# Shared.net
KiCad netlist of a schematic drawn in Altium Designer
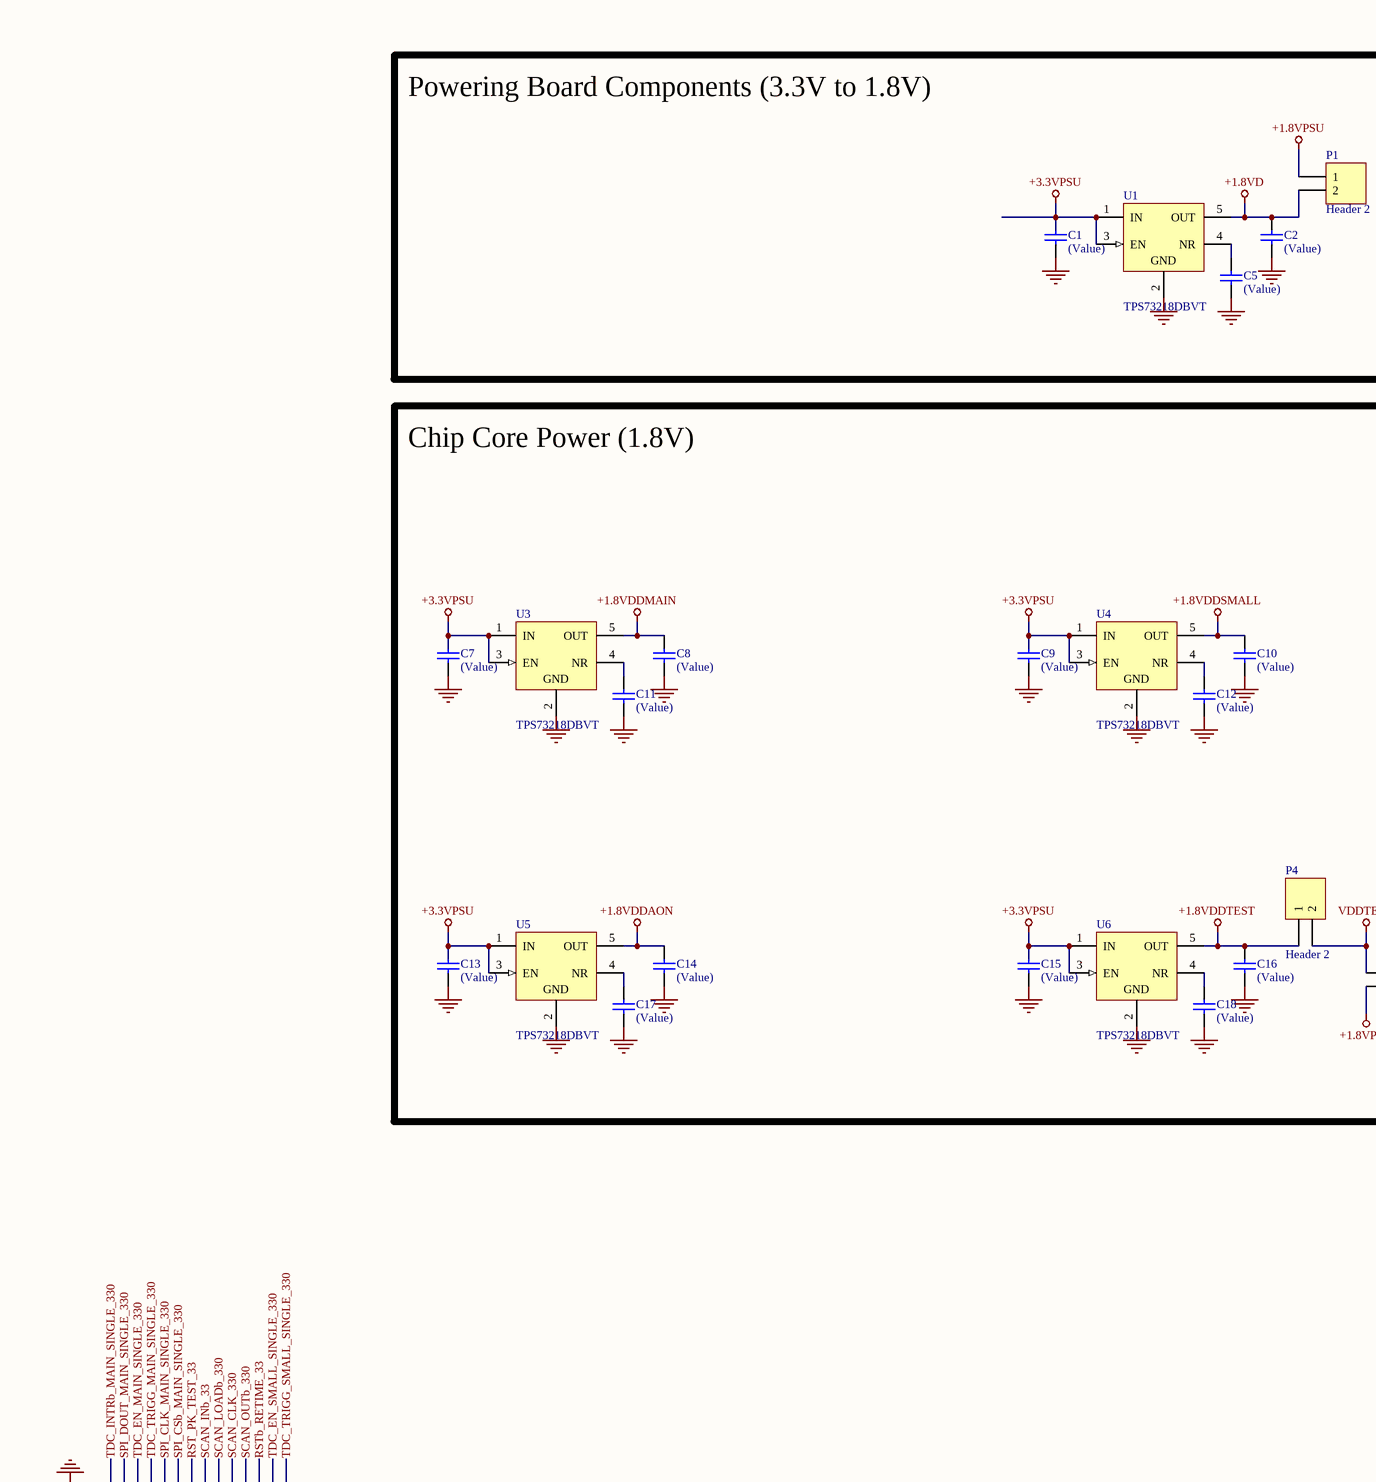
[diagram p0: Shared.SchDoc, top left]
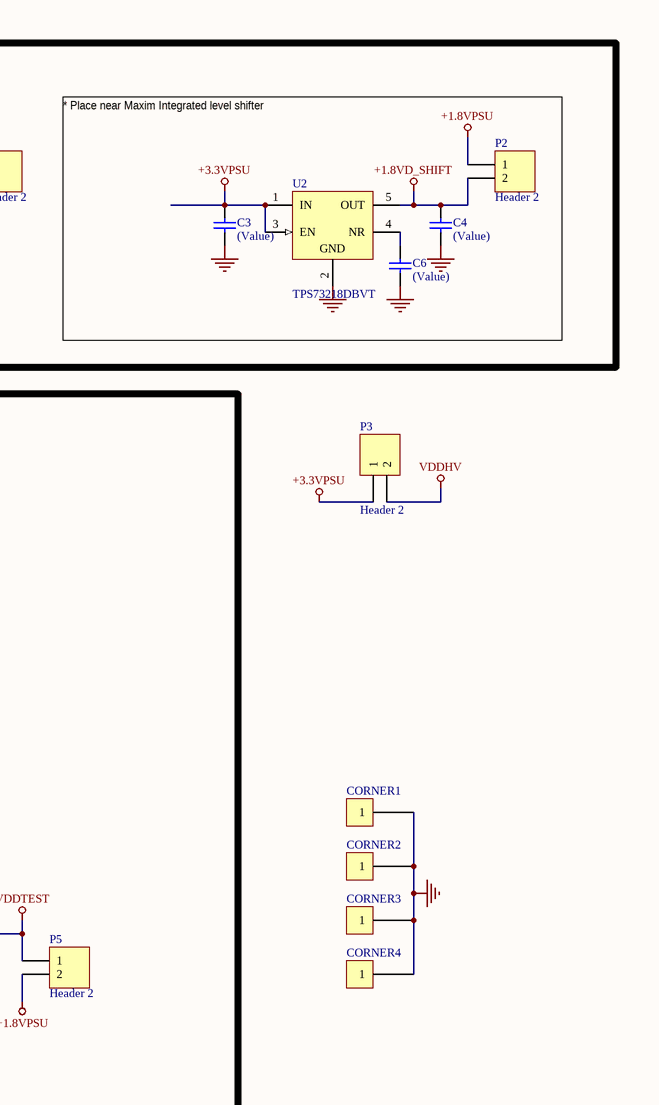
[diagram p1: Shared.SchDoc, top right]
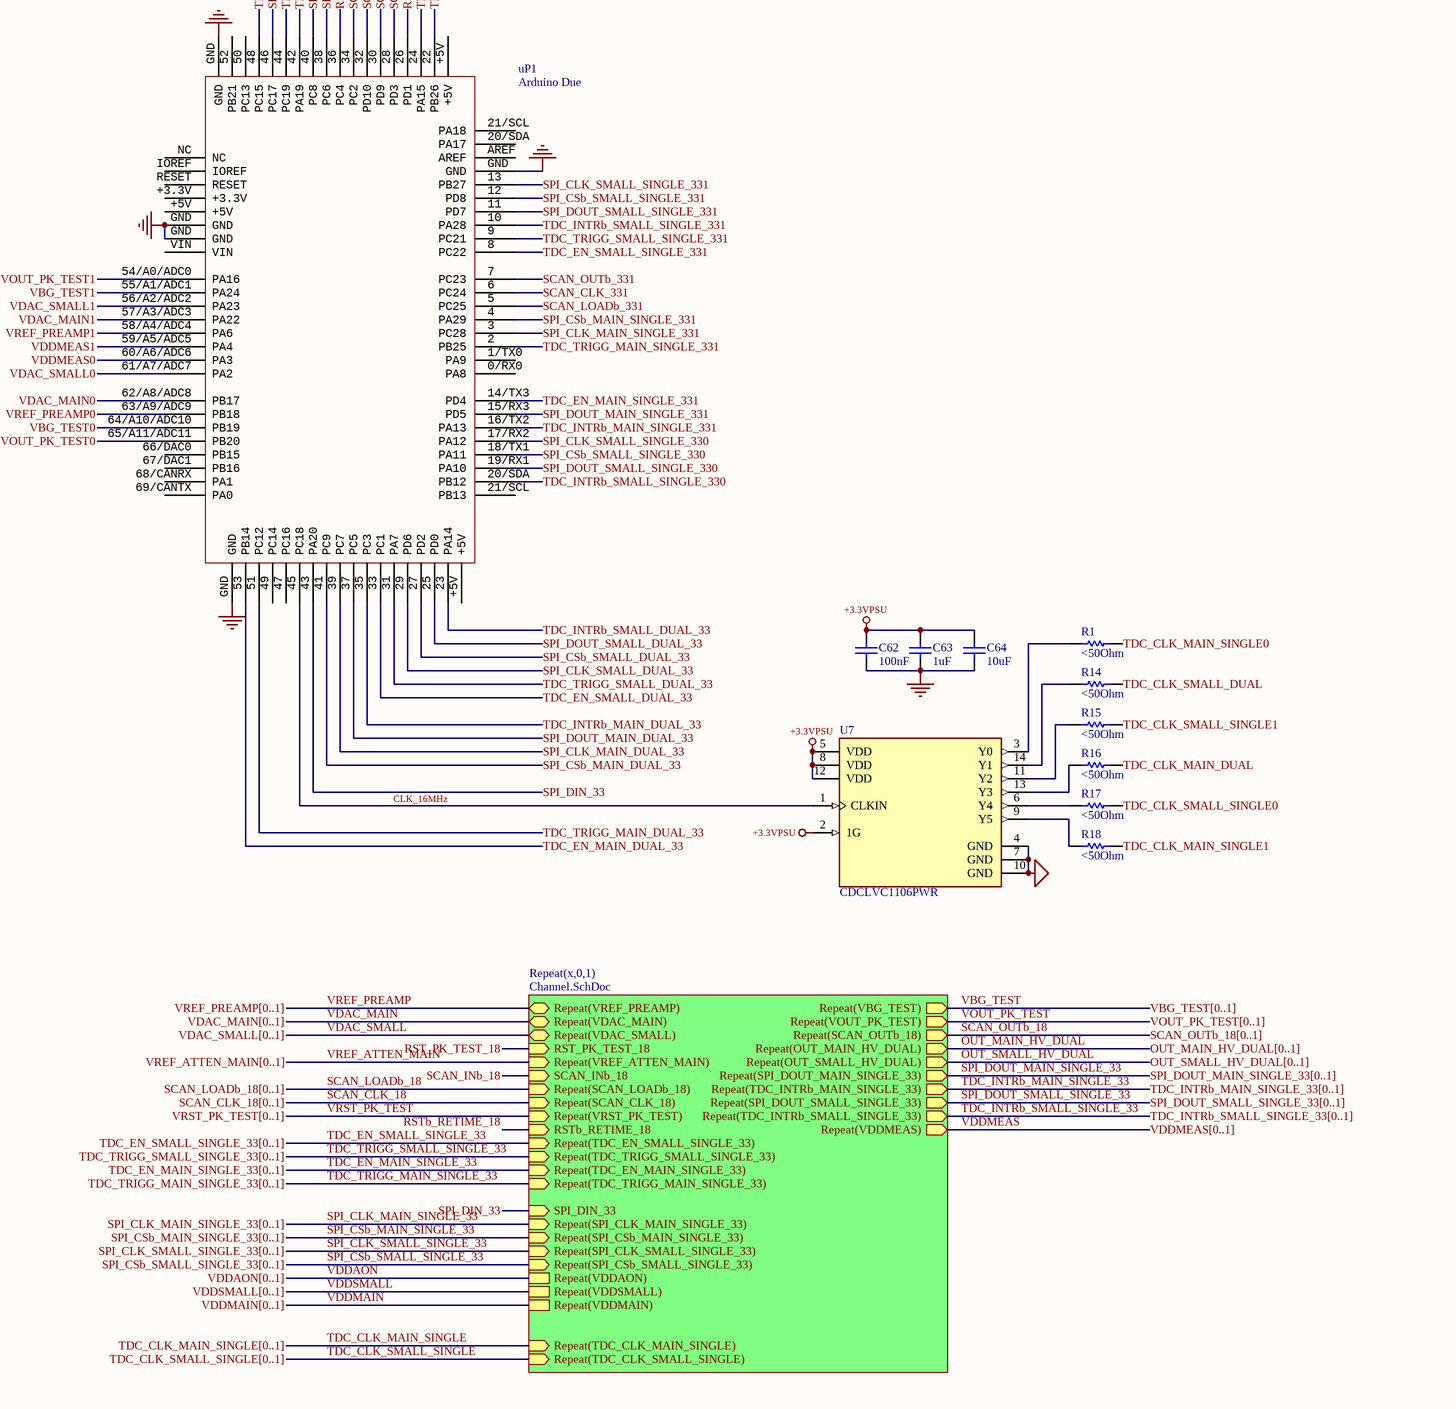
[diagram p2: Shared.SchDoc, bottom left]
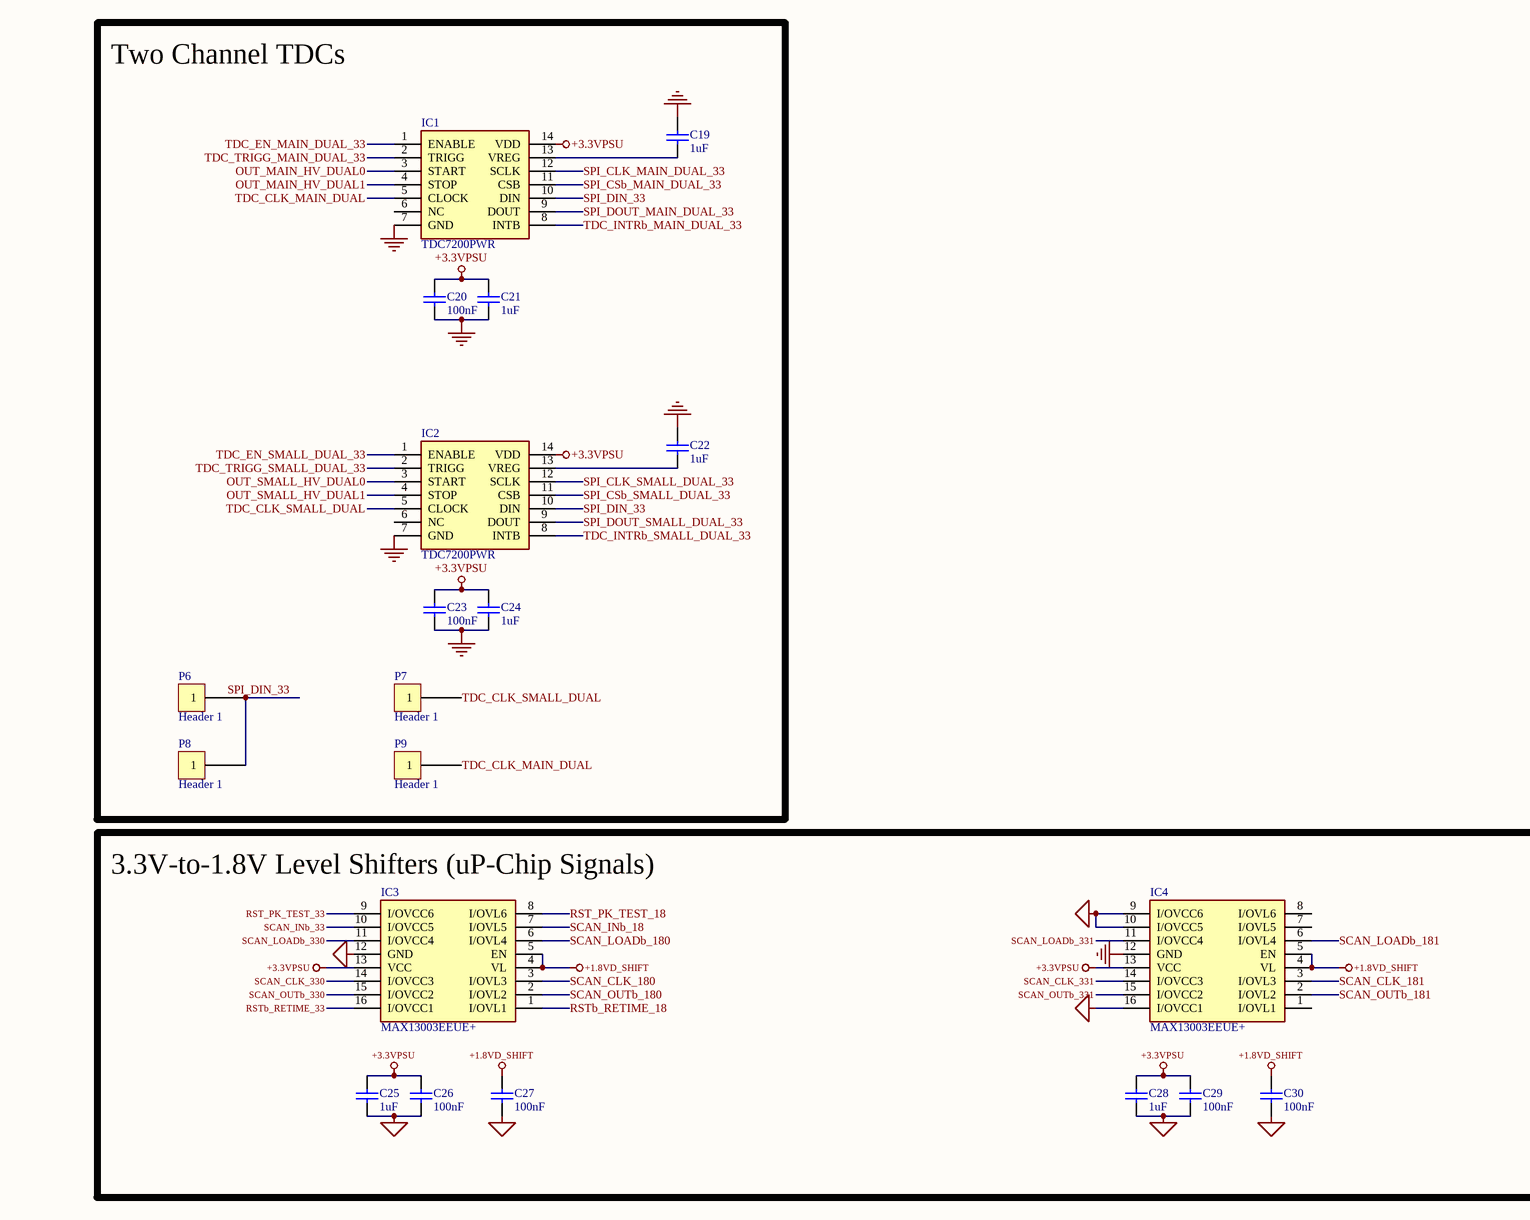
[diagram p3: Shared.SchDoc, bottom right]

(export (version "E")
  (design (tool "Eeschema 10.0.6"))
  (components
    (comp (ref "C1")
      (value "(Value)")
      (footprint "CAPC1608X90X35ML10T15")
      (description "0603")
      (fields (field (name "MANUFACTURER") "Murata"))
      (libsource (lib "Altium Content Vault") (part "CAP-NP-2"))
    )
    (comp (ref "C2")
      (value "(Value)")
      (footprint "CAPC1608X90X35ML10T15")
      (description "0603")
      (fields (field (name "MANUFACTURER") "Murata"))
      (libsource (lib "Altium Content Vault") (part "CAP-NP-2"))
    )
    (comp (ref "C3")
      (value "(Value)")
      (footprint "CAPC1608X90X35ML10T15")
      (description "0603")
      (fields (field (name "MANUFACTURER") "Murata"))
      (libsource (lib "Altium Content Vault") (part "CAP-NP-2"))
    )
    (comp (ref "C4")
      (value "(Value)")
      (footprint "CAPC1608X90X35ML10T15")
      (description "0603")
      (fields (field (name "MANUFACTURER") "Murata"))
      (libsource (lib "Altium Content Vault") (part "CAP-NP-2"))
    )
    (comp (ref "C5")
      (value "(Value)")
      (footprint "CAPC1608X90X35ML10T15")
      (description "0603")
      (fields (field (name "MANUFACTURER") "Murata"))
      (libsource (lib "Altium Content Vault") (part "CAP-NP-2"))
    )
    (comp (ref "C6")
      (value "(Value)")
      (footprint "CAPC1608X90X35ML10T15")
      (description "0603")
      (fields (field (name "MANUFACTURER") "Murata"))
      (libsource (lib "Altium Content Vault") (part "CAP-NP-2"))
    )
    (comp (ref "C7")
      (value "(Value)")
      (footprint "CAPC1608X90X35ML10T15")
      (description "0603")
      (fields (field (name "MANUFACTURER") "Murata"))
      (libsource (lib "Altium Content Vault") (part "CAP-NP-2"))
    )
    (comp (ref "C8")
      (value "(Value)")
      (footprint "CAPC1608X90X35ML10T15")
      (description "0603")
      (fields (field (name "MANUFACTURER") "Murata"))
      (libsource (lib "Altium Content Vault") (part "CAP-NP-2"))
    )
    (comp (ref "C9")
      (value "(Value)")
      (footprint "CAPC1608X90X35ML10T15")
      (description "0603")
      (fields (field (name "MANUFACTURER") "Murata"))
      (libsource (lib "Altium Content Vault") (part "CAP-NP-2"))
    )
    (comp (ref "C10")
      (value "(Value)")
      (footprint "CAPC1608X90X35ML10T15")
      (description "0603")
      (fields (field (name "MANUFACTURER") "Murata"))
      (libsource (lib "Altium Content Vault") (part "CAP-NP-2"))
    )
    (comp (ref "C11")
      (value "(Value)")
      (footprint "CAPC1608X90X35ML10T15")
      (description "0603")
      (fields (field (name "MANUFACTURER") "Murata"))
      (libsource (lib "Altium Content Vault") (part "CAP-NP-2"))
    )
    (comp (ref "C12")
      (value "(Value)")
      (footprint "CAPC1608X90X35ML10T15")
      (description "0603")
      (fields (field (name "MANUFACTURER") "Murata"))
      (libsource (lib "Altium Content Vault") (part "CAP-NP-2"))
    )
    (comp (ref "C13")
      (value "(Value)")
      (footprint "CAPC1608X90X35ML10T15")
      (description "0603")
      (fields (field (name "MANUFACTURER") "Murata"))
      (libsource (lib "Altium Content Vault") (part "CAP-NP-2"))
    )
    (comp (ref "C14")
      (value "(Value)")
      (footprint "CAPC1608X90X35ML10T15")
      (description "0603")
      (fields (field (name "MANUFACTURER") "Murata"))
      (libsource (lib "Altium Content Vault") (part "CAP-NP-2"))
    )
    (comp (ref "C15")
      (value "(Value)")
      (footprint "CAPC1608X90X35ML10T15")
      (description "0603")
      (fields (field (name "MANUFACTURER") "Murata"))
      (libsource (lib "Altium Content Vault") (part "CAP-NP-2"))
    )
    (comp (ref "C16")
      (value "(Value)")
      (footprint "CAPC1608X90X35ML10T15")
      (description "0603")
      (fields (field (name "MANUFACTURER") "Murata"))
      (libsource (lib "Altium Content Vault") (part "CAP-NP-2"))
    )
    (comp (ref "C17")
      (value "(Value)")
      (footprint "CAPC1608X90X35ML10T15")
      (description "0603")
      (fields (field (name "MANUFACTURER") "Murata"))
      (libsource (lib "Altium Content Vault") (part "CAP-NP-2"))
    )
    (comp (ref "C18")
      (value "(Value)")
      (footprint "CAPC1608X90X35ML10T15")
      (description "0603")
      (fields (field (name "MANUFACTURER") "Murata"))
      (libsource (lib "Altium Content Vault") (part "CAP-NP-2"))
    )
    (comp (ref "C19")
      (value "1uF")
      (footprint "CAPC1608X90X35ML10T15")
      (description "0603")
      (fields (field (name "MANUFACTURER") "Murata"))
      (libsource (lib "Altium Content Vault") (part "CAP-NP-2"))
    )
    (comp (ref "C20")
      (value "100nF")
      (footprint "CAPC1608X90X35ML10T15")
      (description "0603")
      (fields (field (name "MANUFACTURER") "Murata"))
      (libsource (lib "Altium Content Vault") (part "CAP-NP-2"))
    )
    (comp (ref "C21")
      (value "1uF")
      (footprint "CAPC1608X90X35ML10T15")
      (description "0603")
      (fields (field (name "MANUFACTURER") "Murata"))
      (libsource (lib "Altium Content Vault") (part "CAP-NP-2"))
    )
    (comp (ref "C22")
      (value "1uF")
      (footprint "CAPC1608X90X35ML10T15")
      (description "0603")
      (fields (field (name "MANUFACTURER") "Murata"))
      (libsource (lib "Altium Content Vault") (part "CAP-NP-2"))
    )
    (comp (ref "C23")
      (value "100nF")
      (footprint "CAPC1608X90X35ML10T15")
      (description "0603")
      (fields (field (name "MANUFACTURER") "Murata"))
      (libsource (lib "Altium Content Vault") (part "CAP-NP-2"))
    )
    (comp (ref "C24")
      (value "1uF")
      (footprint "CAPC1608X90X35ML10T15")
      (description "0603")
      (fields (field (name "MANUFACTURER") "Murata"))
      (libsource (lib "Altium Content Vault") (part "CAP-NP-2"))
    )
    (comp (ref "C25")
      (value "1uF")
      (footprint "CAPC1608X90X35ML10T15")
      (description "0603")
      (fields (field (name "MANUFACTURER") "Murata"))
      (libsource (lib "Altium Content Vault") (part "CAP-NP-2"))
    )
    (comp (ref "C26")
      (value "100nF")
      (footprint "CAPC1608X90X35ML10T15")
      (description "0603")
      (fields (field (name "MANUFACTURER") "Murata"))
      (libsource (lib "Altium Content Vault") (part "CAP-NP-2"))
    )
    (comp (ref "C27")
      (value "100nF")
      (footprint "CAPC1608X90X35ML10T15")
      (description "0603")
      (fields (field (name "MANUFACTURER") "Murata"))
      (libsource (lib "Altium Content Vault") (part "CAP-NP-2"))
    )
    (comp (ref "C28")
      (value "1uF")
      (footprint "CAPC1608X90X35ML10T15")
      (description "0603")
      (fields (field (name "MANUFACTURER") "Murata"))
      (libsource (lib "Altium Content Vault") (part "CAP-NP-2"))
    )
    (comp (ref "C29")
      (value "100nF")
      (footprint "CAPC1608X90X35ML10T15")
      (description "0603")
      (fields (field (name "MANUFACTURER") "Murata"))
      (libsource (lib "Altium Content Vault") (part "CAP-NP-2"))
    )
    (comp (ref "C30")
      (value "100nF")
      (footprint "CAPC1608X90X35ML10T15")
      (description "0603")
      (fields (field (name "MANUFACTURER") "Murata"))
      (libsource (lib "Altium Content Vault") (part "CAP-NP-2"))
    )
    (comp (ref "C62")
      (value "100nF")
      (footprint "CAPC1608X90X35ML10T15")
      (description "0603")
      (fields (field (name "MANUFACTURER") "Murata"))
      (libsource (lib "Altium Content Vault") (part "CAP-NP-2"))
    )
    (comp (ref "C63")
      (value "1uF")
      (footprint "CAPC1608X90X35ML10T15")
      (description "0603")
      (fields (field (name "MANUFACTURER") "Murata"))
      (libsource (lib "Altium Content Vault") (part "CAP-NP-2"))
    )
    (comp (ref "C64")
      (value "10uF")
      (footprint "CAPC1608X90X35ML10T15")
      (description "0603")
      (fields (field (name "MANUFACTURER") "Murata"))
      (libsource (lib "Altium Content Vault") (part "CAP-NP-2"))
    )
    (comp (ref "CORNER1")
      (value "Corner Mount")
      (footprint "CornerMount")
      (libsource (lib "intlib") (part "Corner Mount"))
    )
    (comp (ref "CORNER2")
      (value "Corner Mount")
      (footprint "CornerMount")
      (libsource (lib "intlib") (part "Corner Mount"))
    )
    (comp (ref "CORNER3")
      (value "Corner Mount")
      (footprint "CornerMount")
      (libsource (lib "intlib") (part "Corner Mount"))
    )
    (comp (ref "CORNER4")
      (value "Corner Mount")
      (footprint "CornerMount")
      (libsource (lib "intlib") (part "Corner Mount"))
    )
    (comp (ref "IC1")
      (value "TDC7200PWR")
      (footprint "SamacSys:SOP65P640X120-14N")
      (description "Integrated Circuit")
      (libsource (lib "*") (part "TDC7200PWR"))
    )
    (comp (ref "IC2")
      (value "TDC7200PWR")
      (footprint "SamacSys:SOP65P640X120-14N")
      (description "Integrated Circuit")
      (libsource (lib "*") (part "TDC7200PWR"))
    )
    (comp (ref "IC3")
      (value "MAX13003EEUE+")
      (footprint "SamacSys:SOP65P640X110-16N")
      (description "Integrated Circuit")
      (libsource (lib "*") (part "MAX13003EEUE+"))
    )
    (comp (ref "IC4")
      (value "MAX13003EEUE+")
      (footprint "SamacSys:SOP65P640X110-16N")
      (description "Integrated Circuit")
      (libsource (lib "*") (part "MAX13003EEUE+"))
    )
    (comp (ref "P1")
      (value "Header 2")
      (footprint "HDR1X2")
      (description "Header, 2-Pin")
      (fields (field (name "PUBLISHER") "Altium Limited"))
      (libsource (lib "") (part "Header 2_1"))
    )
    (comp (ref "P2")
      (value "Header 2")
      (footprint "HDR1X2")
      (description "Header, 2-Pin")
      (fields (field (name "PUBLISHER") "Altium Limited"))
      (libsource (lib "") (part "Header 2_1"))
    )
    (comp (ref "P3")
      (value "Header 2")
      (footprint "HDR1X2")
      (description "Header, 2-Pin")
      (fields (field (name "PUBLISHER") "Altium Limited"))
      (libsource (lib "Miscellaneous Connectors") (part "Header 2"))
    )
    (comp (ref "P4")
      (value "Header 2")
      (footprint "HDR1X2")
      (description "Header, 2-Pin")
      (fields (field (name "PUBLISHER") "Altium Limited"))
      (libsource (lib "Miscellaneous Connectors") (part "Header 2"))
    )
    (comp (ref "P5")
      (value "Header 2")
      (footprint "HDR1X2")
      (description "Header, 2-Pin")
      (fields (field (name "PUBLISHER") "Altium Limited"))
      (libsource (lib "") (part "Header 2_1"))
    )
    (comp (ref "P6") (value "Header 1") (footprint "Header1") (libsource (lib "intlib") (part "Header 1")))
    (comp (ref "P7") (value "Header 1") (footprint "Header1") (libsource (lib "intlib") (part "Header 1")))
    (comp (ref "P8") (value "Header 1") (footprint "Header1") (libsource (lib "intlib") (part "Header 1")))
    (comp (ref "P9") (value "Header 1") (footprint "Header1") (libsource (lib "intlib") (part "Header 1")))
    (comp (ref "R1")
      (value "<50Ohm")
      (footprint "RESC1609X50X30NL8T20")
      (description "0603")
      (fields (field (name "MANUFACTURER") "Vishay Semiconductor"))
      (libsource (lib "Altium Content Vault") (part "RES-2"))
    )
    (comp (ref "R14")
      (value "<50Ohm")
      (footprint "RESC1609X50X30NL8T20")
      (description "0603")
      (fields (field (name "MANUFACTURER") "Vishay Semiconductor"))
      (libsource (lib "Altium Content Vault") (part "RES-2"))
    )
    (comp (ref "R15")
      (value "<50Ohm")
      (footprint "RESC1609X50X30NL8T20")
      (description "0603")
      (fields (field (name "MANUFACTURER") "Vishay Semiconductor"))
      (libsource (lib "Altium Content Vault") (part "RES-2"))
    )
    (comp (ref "R16")
      (value "<50Ohm")
      (footprint "RESC1609X50X30NL8T20")
      (description "0603")
      (fields (field (name "MANUFACTURER") "Vishay Semiconductor"))
      (libsource (lib "Altium Content Vault") (part "RES-2"))
    )
    (comp (ref "R17")
      (value "<50Ohm")
      (footprint "RESC1609X50X30NL8T20")
      (description "0603")
      (fields (field (name "MANUFACTURER") "Vishay Semiconductor"))
      (libsource (lib "Altium Content Vault") (part "RES-2"))
    )
    (comp (ref "R18")
      (value "<50Ohm")
      (footprint "RESC1609X50X30NL8T20")
      (description "0603")
      (fields (field (name "MANUFACTURER") "Vishay Semiconductor"))
      (libsource (lib "Altium Content Vault") (part "RES-2"))
    )
    (comp (ref "U1")
      (value "TPS73218DBVT")
      (footprint "DBV0005A_N")
      (fields (field (name "MANUFACTURER") "Texas Instruments"))
      (libsource (lib "Altium Content Vault") (part "TI-TPS79NXX-YYSOT5"))
    )
    (comp (ref "U2")
      (value "TPS73218DBVT")
      (footprint "DBV0005A_N")
      (fields (field (name "MANUFACTURER") "Texas Instruments"))
      (libsource (lib "Altium Content Vault") (part "TI-TPS79NXX-YYSOT5"))
    )
    (comp (ref "U3")
      (value "TPS73218DBVT")
      (footprint "DBV0005A_N")
      (fields (field (name "MANUFACTURER") "Texas Instruments"))
      (libsource (lib "Altium Content Vault") (part "TI-TPS79NXX-YYSOT5"))
    )
    (comp (ref "U4")
      (value "TPS73218DBVT")
      (footprint "DBV0005A_N")
      (fields (field (name "MANUFACTURER") "Texas Instruments"))
      (libsource (lib "Altium Content Vault") (part "TI-TPS79NXX-YYSOT5"))
    )
    (comp (ref "U5")
      (value "TPS73218DBVT")
      (footprint "DBV0005A_N")
      (fields (field (name "MANUFACTURER") "Texas Instruments"))
      (libsource (lib "Altium Content Vault") (part "TI-TPS79NXX-YYSOT5"))
    )
    (comp (ref "U6")
      (value "TPS73218DBVT")
      (footprint "DBV0005A_N")
      (fields (field (name "MANUFACTURER") "Texas Instruments"))
      (libsource (lib "Altium Content Vault") (part "TI-TPS79NXX-YYSOT5"))
    )
    (comp (ref "U7")
      (value "CDCLVC1106PWR")
      (footprint "FP-PW0014A-MFG")
      (description "IC CLK BUFFER 1:6 250MHZ 14TSSOP")
      (fields
        (field (name "MANUFACTURER") "Texas Instruments")
        (field (name "OCTOPART") "https://octopart.com/cdclvc1106pwr-texas+instruments-18629865")
      )
      (libsource (lib "Altium Content Vault") (part "c658b08e815d5ba30375de9a23295a1"))
    )
    (comp (ref "uP1")
      (value "Arduino Due")
      (footprint "Arduino Due")
      (libsource (lib "intlib") (part "Arduino Due"))
    )
  )
  (nets
    (net (code "11") (name "+1.8VD") (class "Default")
      (node (ref "C2") (pin "1") (pinfunction "1_1") (pintype "passive"))
      (node (ref "P1") (pin "2") (pinfunction "2_2") (pintype "passive"))
      (node (ref "U1") (pin "5") (pinfunction "OUT_5") (pintype "power_in"))
    )
    (net (code "12") (name "+1.8VDDAON") (class "Default")
      (node (ref "C14") (pin "1") (pinfunction "1_1") (pintype "passive"))
      (node (ref "U5") (pin "5") (pinfunction "OUT_5") (pintype "power_in"))
    )
    (net (code "13") (name "+1.8VDDMAIN") (class "Default")
      (node (ref "C8") (pin "1") (pinfunction "1_1") (pintype "passive"))
      (node (ref "U3") (pin "5") (pinfunction "OUT_5") (pintype "power_in"))
    )
    (net (code "14") (name "+1.8VDDSMALL") (class "Default")
      (node (ref "C10") (pin "1") (pinfunction "1_1") (pintype "passive"))
      (node (ref "U4") (pin "5") (pinfunction "OUT_5") (pintype "power_in"))
    )
    (net (code "15") (name "+1.8VDDTEST") (class "Default")
      (node (ref "C16") (pin "1") (pinfunction "1_1") (pintype "passive"))
      (node (ref "P4") (pin "1") (pinfunction "1_1") (pintype "passive"))
      (node (ref "U6") (pin "5") (pinfunction "OUT_5") (pintype "power_in"))
    )
    (net (code "16") (name "+1.8VD_SHIFT") (class "Default")
      (node (ref "C27") (pin "1") (pinfunction "1_1") (pintype "passive"))
      (node (ref "C30") (pin "1") (pinfunction "1_1") (pintype "passive"))
      (node (ref "C4") (pin "1") (pinfunction "1_1") (pintype "passive"))
      (node (ref "IC3") (pin "4") (pinfunction "VL_4") (pintype "passive"))
      (node (ref "IC3") (pin "5") (pinfunction "EN_5") (pintype "passive"))
      (node (ref "IC4") (pin "4") (pinfunction "VL_4") (pintype "passive"))
      (node (ref "IC4") (pin "5") (pinfunction "EN_5") (pintype "passive"))
      (node (ref "P2") (pin "2") (pinfunction "2_2") (pintype "passive"))
      (node (ref "U2") (pin "5") (pinfunction "OUT_5") (pintype "power_in"))
    )
    (net (code "17") (name "+1.8VPSU") (class "Default")
      (node (ref "P1") (pin "1") (pinfunction "1_1") (pintype "passive"))
      (node (ref "P2") (pin "1") (pinfunction "1_1") (pintype "passive"))
      (node (ref "P5") (pin "2") (pinfunction "2_2") (pintype "passive"))
    )
    (net (code "18") (name "+3.3VPSU") (class "Default")
      (node (ref "C1") (pin "1") (pinfunction "1_1") (pintype "passive"))
      (node (ref "C13") (pin "1") (pinfunction "1_1") (pintype "passive"))
      (node (ref "C15") (pin "1") (pinfunction "1_1") (pintype "passive"))
      (node (ref "C20") (pin "1") (pinfunction "1_1") (pintype "passive"))
      (node (ref "C21") (pin "1") (pinfunction "1_1") (pintype "passive"))
      (node (ref "C23") (pin "1") (pinfunction "1_1") (pintype "passive"))
      (node (ref "C24") (pin "1") (pinfunction "1_1") (pintype "passive"))
      (node (ref "C25") (pin "2") (pinfunction "2_2") (pintype "passive"))
      (node (ref "C26") (pin "2") (pinfunction "2_2") (pintype "passive"))
      (node (ref "C28") (pin "2") (pinfunction "2_2") (pintype "passive"))
      (node (ref "C29") (pin "2") (pinfunction "2_2") (pintype "passive"))
      (node (ref "C3") (pin "1") (pinfunction "1_1") (pintype "passive"))
      (node (ref "C62") (pin "1") (pinfunction "1_1") (pintype "passive"))
      (node (ref "C63") (pin "1") (pinfunction "1_1") (pintype "passive"))
      (node (ref "C64") (pin "1") (pinfunction "1_1") (pintype "passive"))
      (node (ref "C7") (pin "1") (pinfunction "1_1") (pintype "passive"))
      (node (ref "C9") (pin "1") (pinfunction "1_1") (pintype "passive"))
      (node (ref "IC1") (pin "14") (pinfunction "VDD_14") (pintype "passive"))
      (node (ref "IC2") (pin "14") (pinfunction "VDD_14") (pintype "passive"))
      (node (ref "IC3") (pin "13") (pinfunction "VCC_13") (pintype "passive"))
      (node (ref "IC4") (pin "13") (pinfunction "VCC_13") (pintype "passive"))
      (node (ref "P3") (pin "1") (pinfunction "1_1") (pintype "passive"))
      (node (ref "U1") (pin "1") (pinfunction "IN_1") (pintype "power_in"))
      (node (ref "U1") (pin "3") (pinfunction "EN_3") (pintype "input"))
      (node (ref "U2") (pin "1") (pinfunction "IN_1") (pintype "power_in"))
      (node (ref "U2") (pin "3") (pinfunction "EN_3") (pintype "input"))
      (node (ref "U3") (pin "1") (pinfunction "IN_1") (pintype "power_in"))
      (node (ref "U3") (pin "3") (pinfunction "EN_3") (pintype "input"))
      (node (ref "U4") (pin "1") (pinfunction "IN_1") (pintype "power_in"))
      (node (ref "U4") (pin "3") (pinfunction "EN_3") (pintype "input"))
      (node (ref "U5") (pin "1") (pinfunction "IN_1") (pintype "power_in"))
      (node (ref "U5") (pin "3") (pinfunction "EN_3") (pintype "input"))
      (node (ref "U6") (pin "1") (pinfunction "IN_1") (pintype "power_in"))
      (node (ref "U6") (pin "3") (pinfunction "EN_3") (pintype "input"))
      (node (ref "U7") (pin "12") (pinfunction "VDD_12") (pintype "power_in"))
      (node (ref "U7") (pin "2") (pinfunction "1G_2") (pintype "input"))
      (node (ref "U7") (pin "5") (pinfunction "VDD_5") (pintype "power_in"))
      (node (ref "U7") (pin "8") (pinfunction "VDD_8") (pintype "power_in"))
    )
    (net (code "19") (name "/CLK_16MHz") (class "Default")
      (node (ref "U7") (pin "1") (pinfunction "CLKIN_1") (pintype "input"))
      (node (ref "uP1") (pin "45") (pinfunction "PC18_45") (pintype "passive"))
    )
    (net (code "21") (name "/OUT_MAIN_HV_DUAL0") (class "Default")
      (node (ref "IC1") (pin "3") (pinfunction "START_3") (pintype "passive"))
    )
    (net (code "22") (name "/OUT_MAIN_HV_DUAL1") (class "Default")
      (node (ref "IC1") (pin "4") (pinfunction "STOP_4") (pintype "passive"))
    )
    (net (code "25") (name "/OUT_SMALL_HV_DUAL0") (class "Default")
      (node (ref "IC2") (pin "3") (pinfunction "START_3") (pintype "passive"))
    )
    (net (code "26") (name "/OUT_SMALL_HV_DUAL1") (class "Default")
      (node (ref "IC2") (pin "4") (pinfunction "STOP_4") (pintype "passive"))
    )
    (net (code "28") (name "/RST_PK_TEST_18") (class "Default")
      (node (ref "IC3") (pin "8") (pinfunction "I/OVL6_8") (pintype "passive"))
    )
    (net (code "29") (name "/RST_PK_TEST_33") (class "Default")
      (node (ref "IC3") (pin "9") (pinfunction "I/OVCC6_9") (pintype "passive"))
      (node (ref "uP1") (pin "36") (pinfunction "PC4_36") (pintype "passive"))
    )
    (net (code "30") (name "/RSTb_RETIME_18") (class "Default")
      (node (ref "IC3") (pin "1") (pinfunction "I/OVL1_1") (pintype "passive"))
    )
    (net (code "31") (name "/RSTb_RETIME_33") (class "Default")
      (node (ref "IC3") (pin "16") (pinfunction "I/OVCC1_16") (pintype "passive"))
      (node (ref "uP1") (pin "26") (pinfunction "PD1_26") (pintype "passive"))
    )
    (net (code "34") (name "/SCAN_CLK_180") (class "Default")
      (node (ref "IC3") (pin "3") (pinfunction "I/OVL3_3") (pintype "passive"))
    )
    (net (code "35") (name "/SCAN_CLK_181") (class "Default")
      (node (ref "IC4") (pin "3") (pinfunction "I/OVL3_3") (pintype "passive"))
    )
    (net (code "36") (name "/SCAN_CLK_330") (class "Default")
      (node (ref "IC3") (pin "14") (pinfunction "I/OVCC3_14") (pintype "passive"))
      (node (ref "uP1") (pin "30") (pinfunction "PD9_30") (pintype "passive"))
    )
    (net (code "37") (name "/SCAN_CLK_331") (class "Default")
      (node (ref "IC4") (pin "14") (pinfunction "I/OVCC3_14") (pintype "passive"))
      (node (ref "uP1") (pin "6") (pinfunction "PC24_6") (pintype "passive"))
    )
    (net (code "38") (name "/SCAN_INb_18") (class "Default")
      (node (ref "IC3") (pin "7") (pinfunction "I/OVL5_7") (pintype "passive"))
    )
    (net (code "39") (name "/SCAN_INb_33") (class "Default")
      (node (ref "IC3") (pin "10") (pinfunction "I/OVCC5_10") (pintype "passive"))
      (node (ref "uP1") (pin "34") (pinfunction "PC2_34") (pintype "passive"))
    )
    (net (code "42") (name "/SCAN_LOADb_180") (class "Default")
      (node (ref "IC3") (pin "6") (pinfunction "I/OVL4_6") (pintype "passive"))
    )
    (net (code "43") (name "/SCAN_LOADb_181") (class "Default")
      (node (ref "IC4") (pin "6") (pinfunction "I/OVL4_6") (pintype "passive"))
    )
    (net (code "44") (name "/SCAN_LOADb_330") (class "Default")
      (node (ref "IC3") (pin "11") (pinfunction "I/OVCC4_11") (pintype "passive"))
      (node (ref "uP1") (pin "32") (pinfunction "PD10_32") (pintype "passive"))
    )
    (net (code "45") (name "/SCAN_LOADb_331") (class "Default")
      (node (ref "IC4") (pin "11") (pinfunction "I/OVCC4_11") (pintype "passive"))
      (node (ref "uP1") (pin "5") (pinfunction "PC25_5") (pintype "passive"))
    )
    (net (code "48") (name "/SCAN_OUTb_180") (class "Default")
      (node (ref "IC3") (pin "2") (pinfunction "I/OVL2_2") (pintype "passive"))
    )
    (net (code "49") (name "/SCAN_OUTb_181") (class "Default")
      (node (ref "IC4") (pin "2") (pinfunction "I/OVL2_2") (pintype "passive"))
    )
    (net (code "50") (name "/SCAN_OUTb_330") (class "Default")
      (node (ref "IC3") (pin "15") (pinfunction "I/OVCC2_15") (pintype "passive"))
      (node (ref "uP1") (pin "28") (pinfunction "PD3_28") (pintype "passive"))
    )
    (net (code "51") (name "/SCAN_OUTb_331") (class "Default")
      (node (ref "IC4") (pin "15") (pinfunction "I/OVCC2_15") (pintype "passive"))
      (node (ref "uP1") (pin "7") (pinfunction "PC23_7") (pintype "passive"))
    )
    (net (code "52") (name "/SPI_CLK_MAIN_DUAL_33") (class "Default")
      (node (ref "IC1") (pin "12") (pinfunction "SCLK_12") (pintype "passive"))
      (node (ref "uP1") (pin "39") (pinfunction "PC7_39") (pintype "passive"))
    )
    (net (code "55") (name "/SPI_CLK_MAIN_SINGLE_330") (class "Default")
      (node (ref "uP1") (pin "40") (pinfunction "PC8_40") (pintype "passive"))
    )
    (net (code "56") (name "/SPI_CLK_MAIN_SINGLE_331") (class "Default")
      (node (ref "uP1") (pin "3") (pinfunction "PC28_3") (pintype "passive"))
    )
    (net (code "57") (name "/SPI_CLK_SMALL_DUAL_33") (class "Default")
      (node (ref "IC2") (pin "12") (pinfunction "SCLK_12") (pintype "passive"))
      (node (ref "uP1") (pin "29") (pinfunction "PD6_29") (pintype "passive"))
    )
    (net (code "60") (name "/SPI_CLK_SMALL_SINGLE_330") (class "Default")
      (node (ref "uP1") (pin "17/RX2") (pinfunction "PA12_17/RX2") (pintype "passive"))
    )
    (net (code "61") (name "/SPI_CLK_SMALL_SINGLE_331") (class "Default")
      (node (ref "uP1") (pin "13") (pinfunction "PB27_13") (pintype "passive"))
    )
    (net (code "62") (name "/SPI_CSb_MAIN_DUAL_33") (class "Default")
      (node (ref "IC1") (pin "11") (pinfunction "CSB_11") (pintype "passive"))
      (node (ref "uP1") (pin "41") (pinfunction "PC9_41") (pintype "passive"))
    )
    (net (code "65") (name "/SPI_CSb_MAIN_SINGLE_330") (class "Default")
      (node (ref "uP1") (pin "38") (pinfunction "PC6_38") (pintype "passive"))
    )
    (net (code "66") (name "/SPI_CSb_MAIN_SINGLE_331") (class "Default")
      (node (ref "uP1") (pin "4") (pinfunction "PA29_4") (pintype "passive"))
    )
    (net (code "67") (name "/SPI_CSb_SMALL_DUAL_33") (class "Default")
      (node (ref "IC2") (pin "11") (pinfunction "CSB_11") (pintype "passive"))
      (node (ref "uP1") (pin "27") (pinfunction "PD2_27") (pintype "passive"))
    )
    (net (code "70") (name "/SPI_CSb_SMALL_SINGLE_330") (class "Default")
      (node (ref "uP1") (pin "18/TX1") (pinfunction "PA11_18/TX1") (pintype "passive"))
    )
    (net (code "71") (name "/SPI_CSb_SMALL_SINGLE_331") (class "Default")
      (node (ref "uP1") (pin "12") (pinfunction "PD8_12") (pintype "passive"))
    )
    (net (code "72") (name "/SPI_DIN_33") (class "Default")
      (node (ref "IC1") (pin "10") (pinfunction "DIN_10") (pintype "passive"))
      (node (ref "IC2") (pin "10") (pinfunction "DIN_10") (pintype "passive"))
      (node (ref "P6") (pin "1") (pinfunction "1_1") (pintype "passive"))
      (node (ref "P8") (pin "1") (pinfunction "1_1") (pintype "passive"))
      (node (ref "uP1") (pin "43") (pinfunction "PA20_43") (pintype "passive"))
    )
    (net (code "73") (name "/SPI_DOUT_MAIN_DUAL_33") (class "Default")
      (node (ref "IC1") (pin "9") (pinfunction "DOUT_9") (pintype "passive"))
      (node (ref "uP1") (pin "37") (pinfunction "PC5_37") (pintype "passive"))
    )
    (net (code "76") (name "/SPI_DOUT_MAIN_SINGLE_330") (class "Default")
      (node (ref "uP1") (pin "46") (pinfunction "PC17_46") (pintype "passive"))
    )
    (net (code "77") (name "/SPI_DOUT_MAIN_SINGLE_331") (class "Default")
      (node (ref "uP1") (pin "15/RX3") (pinfunction "PD5_15/RX3") (pintype "passive"))
    )
    (net (code "78") (name "/SPI_DOUT_SMALL_DUAL_33") (class "Default")
      (node (ref "IC2") (pin "9") (pinfunction "DOUT_9") (pintype "passive"))
      (node (ref "uP1") (pin "25") (pinfunction "PD0_25") (pintype "passive"))
    )
    (net (code "81") (name "/SPI_DOUT_SMALL_SINGLE_330") (class "Default")
      (node (ref "uP1") (pin "19/RX1") (pinfunction "PA10_19/RX1") (pintype "passive"))
    )
    (net (code "82") (name "/SPI_DOUT_SMALL_SINGLE_331") (class "Default")
      (node (ref "uP1") (pin "11") (pinfunction "PD7_11") (pintype "passive"))
    )
    (net (code "83") (name "/TDC_CLK_MAIN_DUAL") (class "Default")
      (node (ref "IC1") (pin "5") (pinfunction "CLOCK_5") (pintype "passive"))
      (node (ref "P9") (pin "1") (pinfunction "1_1") (pintype "passive"))
      (node (ref "R16") (pin "1") (pinfunction "1_1") (pintype "passive"))
    )
    (net (code "85") (name "/TDC_CLK_MAIN_SINGLE0") (class "Default")
      (node (ref "R1") (pin "1") (pinfunction "1_1") (pintype "passive"))
    )
    (net (code "86") (name "/TDC_CLK_MAIN_SINGLE1") (class "Default")
      (node (ref "R18") (pin "1") (pinfunction "1_1") (pintype "passive"))
    )
    (net (code "88") (name "/TDC_CLK_SMALL_DUAL") (class "Default")
      (node (ref "IC2") (pin "5") (pinfunction "CLOCK_5") (pintype "passive"))
      (node (ref "P7") (pin "1") (pinfunction "1_1") (pintype "passive"))
      (node (ref "R14") (pin "1") (pinfunction "1_1") (pintype "passive"))
    )
    (net (code "90") (name "/TDC_CLK_SMALL_SINGLE0") (class "Default")
      (node (ref "R17") (pin "1") (pinfunction "1_1") (pintype "passive"))
    )
    (net (code "91") (name "/TDC_CLK_SMALL_SINGLE1") (class "Default")
      (node (ref "R15") (pin "1") (pinfunction "1_1") (pintype "passive"))
    )
    (net (code "93") (name "/TDC_EN_MAIN_DUAL_33") (class "Default")
      (node (ref "IC1") (pin "1") (pinfunction "ENABLE_1") (pintype "passive"))
      (node (ref "uP1") (pin "53") (pinfunction "PB14_53") (pintype "passive"))
    )
    (net (code "96") (name "/TDC_EN_MAIN_SINGLE_330") (class "Default")
      (node (ref "uP1") (pin "44") (pinfunction "PC19_44") (pintype "passive"))
    )
    (net (code "97") (name "/TDC_EN_MAIN_SINGLE_331") (class "Default")
      (node (ref "uP1") (pin "14/TX3") (pinfunction "PD4_14/TX3") (pintype "passive"))
    )
    (net (code "98") (name "/TDC_EN_SMALL_DUAL_33") (class "Default")
      (node (ref "IC2") (pin "1") (pinfunction "ENABLE_1") (pintype "passive"))
      (node (ref "uP1") (pin "33") (pinfunction "PC1_33") (pintype "passive"))
    )
    (net (code "101") (name "/TDC_EN_SMALL_SINGLE_330") (class "Default")
      (node (ref "uP1") (pin "24") (pinfunction "PA15_24") (pintype "passive"))
    )
    (net (code "102") (name "/TDC_EN_SMALL_SINGLE_331") (class "Default")
      (node (ref "uP1") (pin "8") (pinfunction "PC22_8") (pintype "passive"))
    )
    (net (code "103") (name "/TDC_INTRb_MAIN_DUAL_33") (class "Default")
      (node (ref "IC1") (pin "8") (pinfunction "INTB_8") (pintype "passive"))
      (node (ref "uP1") (pin "35") (pinfunction "PC3_35") (pintype "passive"))
    )
    (net (code "106") (name "/TDC_INTRb_MAIN_SINGLE_330") (class "Default")
      (node (ref "uP1") (pin "48") (pinfunction "PC15_48") (pintype "passive"))
    )
    (net (code "107") (name "/TDC_INTRb_MAIN_SINGLE_331") (class "Default")
      (node (ref "uP1") (pin "16/TX2") (pinfunction "PA13_16/TX2") (pintype "passive"))
    )
    (net (code "108") (name "/TDC_INTRb_SMALL_DUAL_33") (class "Default")
      (node (ref "IC2") (pin "8") (pinfunction "INTB_8") (pintype "passive"))
      (node (ref "uP1") (pin "23") (pinfunction "PA14_23") (pintype "passive"))
    )
    (net (code "111") (name "/TDC_INTRb_SMALL_SINGLE_330") (class "Default")
      (node (ref "uP1") (pin "20/SDA") (pinfunction "PB12_20/SDA") (pintype "passive"))
    )
    (net (code "112") (name "/TDC_INTRb_SMALL_SINGLE_331") (class "Default")
      (node (ref "uP1") (pin "10") (pinfunction "PA28_10") (pintype "passive"))
    )
    (net (code "113") (name "/TDC_TRIGG_MAIN_DUAL_33") (class "Default")
      (node (ref "IC1") (pin "2") (pinfunction "TRIGG_2") (pintype "passive"))
      (node (ref "uP1") (pin "51") (pinfunction "PC12_51") (pintype "passive"))
    )
    (net (code "116") (name "/TDC_TRIGG_MAIN_SINGLE_330") (class "Default")
      (node (ref "uP1") (pin "42") (pinfunction "PA19_42") (pintype "passive"))
    )
    (net (code "117") (name "/TDC_TRIGG_MAIN_SINGLE_331") (class "Default")
      (node (ref "uP1") (pin "2") (pinfunction "PB25_2") (pintype "passive"))
    )
    (net (code "118") (name "/TDC_TRIGG_SMALL_DUAL_33") (class "Default")
      (node (ref "IC2") (pin "2") (pinfunction "TRIGG_2") (pintype "passive"))
      (node (ref "uP1") (pin "31") (pinfunction "PA7_31") (pintype "passive"))
    )
    (net (code "121") (name "/TDC_TRIGG_SMALL_SINGLE_330") (class "Default")
      (node (ref "uP1") (pin "22") (pinfunction "PB26_22") (pintype "passive"))
    )
    (net (code "122") (name "/TDC_TRIGG_SMALL_SINGLE_331") (class "Default")
      (node (ref "uP1") (pin "9") (pinfunction "PC21_9") (pintype "passive"))
    )
    (net (code "124") (name "/VBG_TEST0") (class "Default")
      (node (ref "uP1") (pin "64/A10/ADC10") (pinfunction "PB19_64/A10/ADC10") (pintype "passive"))
    )
    (net (code "125") (name "/VBG_TEST1") (class "Default")
      (node (ref "uP1") (pin "55/A1/ADC1") (pinfunction "PA24_55/A1/ADC1") (pintype "passive"))
    )
    (net (code "128") (name "/VDAC_MAIN0") (class "Default")
      (node (ref "uP1") (pin "62/A8/ADC8") (pinfunction "PB17_62/A8/ADC8") (pintype "passive"))
    )
    (net (code "129") (name "/VDAC_MAIN1") (class "Default")
      (node (ref "uP1") (pin "57/A3/ADC3") (pinfunction "PA22_57/A3/ADC3") (pintype "passive"))
    )
    (net (code "132") (name "/VDAC_SMALL0") (class "Default")
      (node (ref "uP1") (pin "61/A7/ADC7") (pinfunction "PA2_61/A7/ADC7") (pintype "passive"))
    )
    (net (code "133") (name "/VDAC_SMALL1") (class "Default")
      (node (ref "uP1") (pin "56/A2/ADC2") (pinfunction "PA23_56/A2/ADC2") (pintype "passive"))
    )
    (net (code "140") (name "/VDDMEAS0") (class "Default")
      (node (ref "uP1") (pin "60/A6/ADC6") (pinfunction "PA3_60/A6/ADC6") (pintype "passive"))
    )
    (net (code "141") (name "/VDDMEAS1") (class "Default")
      (node (ref "uP1") (pin "59/A5/ADC5") (pinfunction "PA4_59/A5/ADC5") (pintype "passive"))
    )
    (net (code "146") (name "/VOUT_PK_TEST0") (class "Default")
      (node (ref "uP1") (pin "65/A11/ADC11") (pinfunction "PB20_65/A11/ADC11") (pintype "passive"))
    )
    (net (code "147") (name "/VOUT_PK_TEST1") (class "Default")
      (node (ref "uP1") (pin "54/A0/ADC0") (pinfunction "PA16_54/A0/ADC0") (pintype "passive"))
    )
    (net (code "152") (name "/VREF_PREAMP0") (class "Default")
      (node (ref "uP1") (pin "63/A9/ADC9") (pinfunction "PB18_63/A9/ADC9") (pintype "passive"))
    )
    (net (code "153") (name "/VREF_PREAMP1") (class "Default")
      (node (ref "uP1") (pin "58/A4/ADC4") (pinfunction "PA6_58/A4/ADC4") (pintype "passive"))
    )
    (net (code "157") (name "GND") (class "Default")
      (node (ref "C1") (pin "2") (pinfunction "2_2") (pintype "passive"))
      (node (ref "C10") (pin "2") (pinfunction "2_2") (pintype "passive"))
      (node (ref "C11") (pin "2") (pinfunction "2_2") (pintype "passive"))
      (node (ref "C12") (pin "2") (pinfunction "2_2") (pintype "passive"))
      (node (ref "C13") (pin "2") (pinfunction "2_2") (pintype "passive"))
      (node (ref "C14") (pin "2") (pinfunction "2_2") (pintype "passive"))
      (node (ref "C15") (pin "2") (pinfunction "2_2") (pintype "passive"))
      (node (ref "C16") (pin "2") (pinfunction "2_2") (pintype "passive"))
      (node (ref "C17") (pin "2") (pinfunction "2_2") (pintype "passive"))
      (node (ref "C18") (pin "2") (pinfunction "2_2") (pintype "passive"))
      (node (ref "C19") (pin "2") (pinfunction "2_2") (pintype "passive"))
      (node (ref "C2") (pin "2") (pinfunction "2_2") (pintype "passive"))
      (node (ref "C20") (pin "2") (pinfunction "2_2") (pintype "passive"))
      (node (ref "C21") (pin "2") (pinfunction "2_2") (pintype "passive"))
      (node (ref "C22") (pin "2") (pinfunction "2_2") (pintype "passive"))
      (node (ref "C23") (pin "2") (pinfunction "2_2") (pintype "passive"))
      (node (ref "C24") (pin "2") (pinfunction "2_2") (pintype "passive"))
      (node (ref "C25") (pin "1") (pinfunction "1_1") (pintype "passive"))
      (node (ref "C26") (pin "1") (pinfunction "1_1") (pintype "passive"))
      (node (ref "C27") (pin "2") (pinfunction "2_2") (pintype "passive"))
      (node (ref "C28") (pin "1") (pinfunction "1_1") (pintype "passive"))
      (node (ref "C29") (pin "1") (pinfunction "1_1") (pintype "passive"))
      (node (ref "C3") (pin "2") (pinfunction "2_2") (pintype "passive"))
      (node (ref "C30") (pin "2") (pinfunction "2_2") (pintype "passive"))
      (node (ref "C4") (pin "2") (pinfunction "2_2") (pintype "passive"))
      (node (ref "C5") (pin "2") (pinfunction "2_2") (pintype "passive"))
      (node (ref "C6") (pin "2") (pinfunction "2_2") (pintype "passive"))
      (node (ref "C62") (pin "2") (pinfunction "2_2") (pintype "passive"))
      (node (ref "C63") (pin "2") (pinfunction "2_2") (pintype "passive"))
      (node (ref "C64") (pin "2") (pinfunction "2_2") (pintype "passive"))
      (node (ref "C7") (pin "2") (pinfunction "2_2") (pintype "passive"))
      (node (ref "C8") (pin "2") (pinfunction "2_2") (pintype "passive"))
      (node (ref "C9") (pin "2") (pinfunction "2_2") (pintype "passive"))
      (node (ref "CORNER1") (pin "1") (pinfunction "1_1") (pintype "passive"))
      (node (ref "CORNER2") (pin "1") (pinfunction "1_1") (pintype "passive"))
      (node (ref "CORNER3") (pin "1") (pinfunction "1_1") (pintype "passive"))
      (node (ref "CORNER4") (pin "1") (pinfunction "1_1") (pintype "passive"))
      (node (ref "IC1") (pin "7") (pinfunction "GND_7") (pintype "passive"))
      (node (ref "IC2") (pin "7") (pinfunction "GND_7") (pintype "passive"))
      (node (ref "IC3") (pin "12") (pinfunction "GND_12") (pintype "passive"))
      (node (ref "IC4") (pin "10") (pinfunction "I/OVCC5_10") (pintype "passive"))
      (node (ref "IC4") (pin "12") (pinfunction "GND_12") (pintype "passive"))
      (node (ref "IC4") (pin "16") (pinfunction "I/OVCC1_16") (pintype "passive"))
      (node (ref "IC4") (pin "9") (pinfunction "I/OVCC6_9") (pintype "passive"))
      (node (ref "U1") (pin "2") (pinfunction "GND_2") (pintype "power_in"))
      (node (ref "U2") (pin "2") (pinfunction "GND_2") (pintype "power_in"))
      (node (ref "U3") (pin "2") (pinfunction "GND_2") (pintype "power_in"))
      (node (ref "U4") (pin "2") (pinfunction "GND_2") (pintype "power_in"))
      (node (ref "U5") (pin "2") (pinfunction "GND_2") (pintype "power_in"))
      (node (ref "U6") (pin "2") (pinfunction "GND_2") (pintype "power_in"))
      (node (ref "U7") (pin "10") (pinfunction "GND_10") (pintype "power_in"))
      (node (ref "U7") (pin "4") (pinfunction "GND_4") (pintype "power_in"))
      (node (ref "U7") (pin "7") (pinfunction "GND_7") (pintype "power_in"))
      (node (ref "uP1") (pin "GND") (pinfunction "GND_GND") (pintype "passive"))
    )
    (net (code "158") (name "Net-(IC1-VREG)") (class "Default")
      (node (ref "C19") (pin "1") (pinfunction "1_1") (pintype "passive"))
      (node (ref "IC1") (pin "13") (pinfunction "VREG_13") (pintype "passive"))
    )
    (net (code "159") (name "Net-(IC2-VREG)") (class "Default")
      (node (ref "C22") (pin "1") (pinfunction "1_1") (pintype "passive"))
      (node (ref "IC2") (pin "13") (pinfunction "VREG_13") (pintype "passive"))
    )
    (net (code "160") (name "Net-(U1-NR)") (class "Default")
      (node (ref "C5") (pin "1") (pinfunction "1_1") (pintype "passive"))
      (node (ref "U1") (pin "4") (pinfunction "NR_4") (pintype "passive"))
    )
    (net (code "161") (name "Net-(U2-NR)") (class "Default")
      (node (ref "C6") (pin "1") (pinfunction "1_1") (pintype "passive"))
      (node (ref "U2") (pin "4") (pinfunction "NR_4") (pintype "passive"))
    )
    (net (code "162") (name "Net-(U3-NR)") (class "Default")
      (node (ref "C11") (pin "1") (pinfunction "1_1") (pintype "passive"))
      (node (ref "U3") (pin "4") (pinfunction "NR_4") (pintype "passive"))
    )
    (net (code "163") (name "Net-(U4-NR)") (class "Default")
      (node (ref "C12") (pin "1") (pinfunction "1_1") (pintype "passive"))
      (node (ref "U4") (pin "4") (pinfunction "NR_4") (pintype "passive"))
    )
    (net (code "164") (name "Net-(U5-NR)") (class "Default")
      (node (ref "C17") (pin "1") (pinfunction "1_1") (pintype "passive"))
      (node (ref "U5") (pin "4") (pinfunction "NR_4") (pintype "passive"))
    )
    (net (code "165") (name "Net-(U6-NR)") (class "Default")
      (node (ref "C18") (pin "1") (pinfunction "1_1") (pintype "passive"))
      (node (ref "U6") (pin "4") (pinfunction "NR_4") (pintype "passive"))
    )
    (net (code "166") (name "Net-(U7-Y0)") (class "Default")
      (node (ref "R1") (pin "2") (pinfunction "2_2") (pintype "passive"))
      (node (ref "U7") (pin "3") (pinfunction "Y0_3") (pintype "output"))
    )
    (net (code "167") (name "Net-(U7-Y1)") (class "Default")
      (node (ref "R14") (pin "2") (pinfunction "2_2") (pintype "passive"))
      (node (ref "U7") (pin "14") (pinfunction "Y1_14") (pintype "output"))
    )
    (net (code "168") (name "Net-(U7-Y2)") (class "Default")
      (node (ref "R15") (pin "2") (pinfunction "2_2") (pintype "passive"))
      (node (ref "U7") (pin "11") (pinfunction "Y2_11") (pintype "output"))
    )
    (net (code "169") (name "Net-(U7-Y3)") (class "Default")
      (node (ref "R16") (pin "2") (pinfunction "2_2") (pintype "passive"))
      (node (ref "U7") (pin "13") (pinfunction "Y3_13") (pintype "output"))
    )
    (net (code "170") (name "Net-(U7-Y4)") (class "Default")
      (node (ref "R17") (pin "2") (pinfunction "2_2") (pintype "passive"))
      (node (ref "U7") (pin "6") (pinfunction "Y4_6") (pintype "output"))
    )
    (net (code "171") (name "Net-(U7-Y5)") (class "Default")
      (node (ref "R18") (pin "2") (pinfunction "2_2") (pintype "passive"))
      (node (ref "U7") (pin "9") (pinfunction "Y5_9") (pintype "output"))
    )
    (net (code "172") (name "VDDHV") (class "Default")
      (node (ref "P3") (pin "2") (pinfunction "2_2") (pintype "passive"))
    )
    (net (code "173") (name "VDDTEST") (class "Default")
      (node (ref "P4") (pin "2") (pinfunction "2_2") (pintype "passive"))
      (node (ref "P5") (pin "1") (pinfunction "1_1") (pintype "passive"))
    )
    (net (code "174") (name "unconnected-(IC1-NC-Pad6)") (class "Default")
      (node (ref "IC1") (pin "6") (pinfunction "NC_6") (pintype "passive"))
    )
    (net (code "175") (name "unconnected-(IC2-NC-Pad6)") (class "Default")
      (node (ref "IC2") (pin "6") (pinfunction "NC_6") (pintype "passive"))
    )
    (net (code "176") (name "unconnected-(IC4-I{slash}OVL1-Pad1)") (class "Default")
      (node (ref "IC4") (pin "1") (pinfunction "I/OVL1_1") (pintype "passive"))
    )
    (net (code "177") (name "unconnected-(IC4-I{slash}OVL5-Pad7)") (class "Default")
      (node (ref "IC4") (pin "7") (pinfunction "I/OVL5_7") (pintype "passive"))
    )
    (net (code "178") (name "unconnected-(IC4-I{slash}OVL6-Pad8)") (class "Default")
      (node (ref "IC4") (pin "8") (pinfunction "I/OVL6_8") (pintype "passive"))
    )
    (net (code "179") (name "unconnected-(uP1-PA0-Pad69{slash}CANTX)") (class "Default")
      (node (ref "uP1") (pin "69/CANTX") (pinfunction "PA0_69/CANTX") (pintype "passive"))
    )
    (net (code "180") (name "unconnected-(uP1-PA1-Pad68{slash}CANRX)") (class "Default")
      (node (ref "uP1") (pin "68/CANRX") (pinfunction "PA1_68/CANRX") (pintype "passive"))
    )
    (net (code "181") (name "unconnected-(uP1-PA8-Pad0{slash}RX0)") (class "Default")
      (node (ref "uP1") (pin "0/RX0") (pinfunction "PA8_0/RX0") (pintype "passive"))
    )
    (net (code "182") (name "unconnected-(uP1-PA9-Pad1{slash}TX0)") (class "Default")
      (node (ref "uP1") (pin "1/TX0") (pinfunction "PA9_1/TX0") (pintype "passive"))
    )
    (net (code "183") (name "unconnected-(uP1-PA17-Pad20{slash}SDA)") (class "Default")
      (node (ref "uP1") (pin "20/SDA") (pinfunction "PA17_20/SDA") (pintype "passive"))
    )
    (net (code "184") (name "unconnected-(uP1-PA18-Pad21{slash}SCL)") (class "Default")
      (node (ref "uP1") (pin "21/SCL") (pinfunction "PA18_21/SCL") (pintype "passive"))
    )
    (net (code "185") (name "unconnected-(uP1-PB13-Pad21{slash}SCL)") (class "Default")
      (node (ref "uP1") (pin "21/SCL") (pinfunction "PB13_21/SCL") (pintype "passive"))
    )
    (net (code "186") (name "unconnected-(uP1-PB15-Pad66{slash}DAC0)") (class "Default")
      (node (ref "uP1") (pin "66/DAC0") (pinfunction "PB15_66/DAC0") (pintype "passive"))
    )
    (net (code "187") (name "unconnected-(uP1-PB16-Pad67{slash}DAC1)") (class "Default")
      (node (ref "uP1") (pin "67/DAC1") (pinfunction "PB16_67/DAC1") (pintype "passive"))
    )
    (net (code "188") (name "unconnected-(uP1-PB21-Pad52)") (class "Default")
      (node (ref "uP1") (pin "52") (pinfunction "PB21_52") (pintype "passive"))
    )
    (net (code "189") (name "unconnected-(uP1-PC13-Pad50)") (class "Default")
      (node (ref "uP1") (pin "50") (pinfunction "PC13_50") (pintype "passive"))
    )
    (net (code "190") (name "unconnected-(uP1-PC14-Pad49)") (class "Default")
      (node (ref "uP1") (pin "49") (pinfunction "PC14_49") (pintype "passive"))
    )
    (net (code "191") (name "unconnected-(uP1-PC16-Pad47)") (class "Default")
      (node (ref "uP1") (pin "47") (pinfunction "PC16_47") (pintype "passive"))
    )
    (net (code "192") (name "unconnected-(uP1-Pad+3.3V)") (class "Default")
      (node (ref "uP1") (pin "+3.3V") (pinfunction "+3.3V_+3.3V") (pintype "passive"))
    )
    (net (code "193") (name "unconnected-(uP1-Pad+5V)") (class "Default")
      (node (ref "uP1") (pin "+5V") (pinfunction "+5V_+5V") (pintype "passive"))
    )
    (net (code "194") (name "unconnected-(uP1-Pad+5V)_1") (class "Default")
      (node (ref "uP1") (pin "+5V") (pinfunction "+5V_+5V") (pintype "passive"))
    )
    (net (code "195") (name "unconnected-(uP1-Pad+5V)_2") (class "Default")
      (node (ref "uP1") (pin "+5V") (pinfunction "+5V_+5V") (pintype "passive"))
    )
    (net (code "196") (name "unconnected-(uP1-PadAREF)") (class "Default")
      (node (ref "uP1") (pin "AREF") (pinfunction "AREF_AREF") (pintype "passive"))
    )
    (net (code "197") (name "unconnected-(uP1-PadIOREF)") (class "Default")
      (node (ref "uP1") (pin "IOREF") (pinfunction "IOREF_IOREF") (pintype "passive"))
    )
    (net (code "198") (name "unconnected-(uP1-PadNC)") (class "Default")
      (node (ref "uP1") (pin "NC") (pinfunction "NC_NC") (pintype "passive"))
    )
    (net (code "199") (name "unconnected-(uP1-PadRESET)") (class "Default")
      (node (ref "uP1") (pin "RESET") (pinfunction "RESET_RESET") (pintype "passive"))
    )
    (net (code "200") (name "unconnected-(uP1-PadVIN)") (class "Default")
      (node (ref "uP1") (pin "VIN") (pinfunction "VIN_VIN") (pintype "passive"))
    )
  )
)
